# SmartCard.net
KiCad netlist of a schematic drawn in Altium Designer
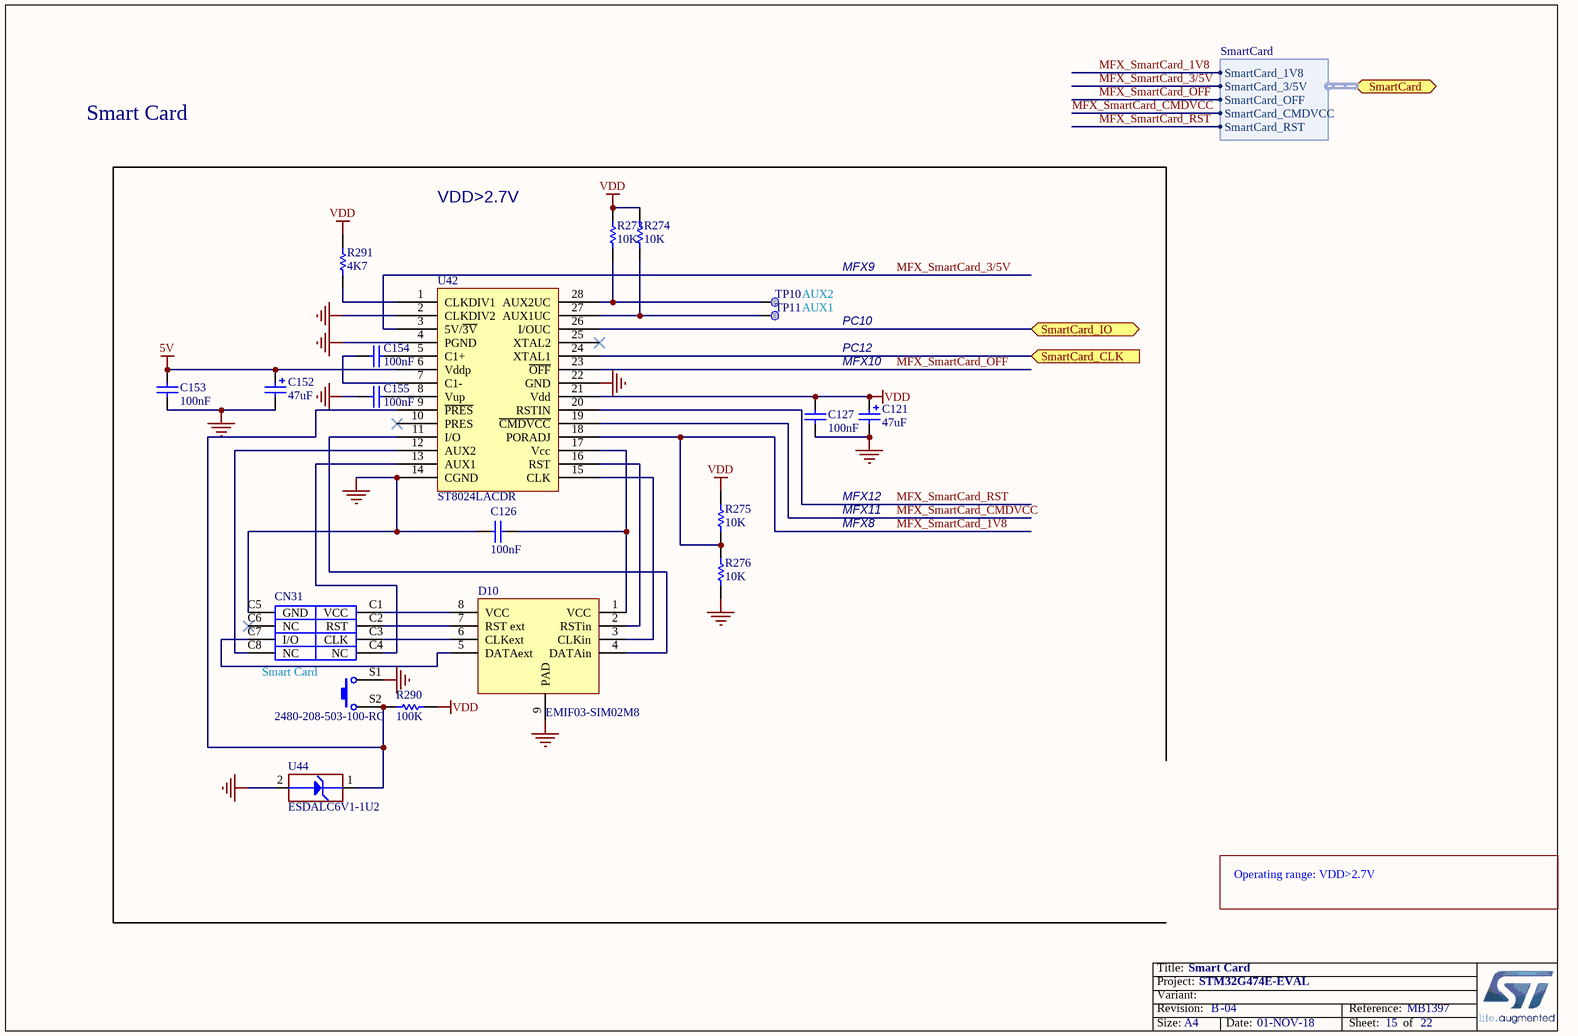
[diagram p0: SmartCard.SchDoc]

(export (version "E")
  (design (tool "Eeschema 10.0.6"))
  (components
    (comp (ref "C121")
      (value "47uF")
      (footprint "CPOL_TAJ-C_2312_H2P6")
      (description "Capacitor, Tantalum, 47uF, 16V, 10%, TypeC")
      (fields
        (field (name "INTERNAL_PART_NUMBER") "MCD-00559")
        (field (name "MANUFACTURER_PART_NUMBER") "TAJC476K016RNJ")
        (field (name "PROVIDED_BY") "SUBCO")
      )
      (libsource (lib "MCD_PARTS_database") (part "Cap_POL_TANA"))
    )
    (comp (ref "C126")
      (value "100nF")
      (footprint "C0603")
      (description "Capacitor, MLCC, 100nF, 16V, X7R, 10%, 0603, T=0,8mm")
      (fields
        (field (name "INTERNAL_PART_NUMBER") "MCD-00211")
        (field (name "MANUFACTURER_PART_NUMBER") "CC0603KRX7R7BB104")
        (field (name "PROVIDED_BY") "SUBCO")
      )
      (libsource (lib "MCD_PARTS_database") (part "Capacitor"))
    )
    (comp (ref "C127")
      (value "100nF")
      (footprint "C0603")
      (description "Capacitor, MLCC, 100nF, 16V, X7R, 10%, 0603, T=0,8mm")
      (fields
        (field (name "INTERNAL_PART_NUMBER") "MCD-00211")
        (field (name "MANUFACTURER_PART_NUMBER") "CC0603KRX7R7BB104")
        (field (name "PROVIDED_BY") "SUBCO")
      )
      (libsource (lib "MCD_PARTS_database") (part "Capacitor"))
    )
    (comp (ref "C152")
      (value "47uF")
      (footprint "CPOL_TAJ-C_2312_H2P6")
      (description "Capacitor, Tantalum, 47uF, 16V, 10%, TypeC")
      (fields
        (field (name "INTERNAL_PART_NUMBER") "MCD-00559")
        (field (name "MANUFACTURER_PART_NUMBER") "TAJC476K016RNJ")
        (field (name "PROVIDED_BY") "SUBCO")
      )
      (libsource (lib "MCD_PARTS_database") (part "Cap_POL_TANA"))
    )
    (comp (ref "C153")
      (value "100nF")
      (footprint "C0603")
      (description "Capacitor, MLCC, 100nF, 16V, X7R, 10%, 0603, T=0,8mm")
      (fields
        (field (name "INTERNAL_PART_NUMBER") "MCD-00211")
        (field (name "MANUFACTURER_PART_NUMBER") "CC0603KRX7R7BB104")
        (field (name "PROVIDED_BY") "SUBCO")
      )
      (libsource (lib "MCD_PARTS_database") (part "Capacitor"))
    )
    (comp (ref "C154")
      (value "100nF")
      (footprint "C0603")
      (description "Capacitor, MLCC, 100nF, 16V, X7R, 10%, 0603, T=0,8mm")
      (fields
        (field (name "INTERNAL_PART_NUMBER") "MCD-00211")
        (field (name "MANUFACTURER_PART_NUMBER") "CC0603KRX7R7BB104")
        (field (name "PROVIDED_BY") "SUBCO")
      )
      (libsource (lib "MCD_PARTS_database") (part "Capacitor"))
    )
    (comp (ref "C155")
      (value "100nF")
      (footprint "C0603")
      (description "Capacitor, MLCC, 100nF, 16V, X7R, 10%, 0603, T=0,8mm")
      (fields
        (field (name "INTERNAL_PART_NUMBER") "MCD-00211")
        (field (name "MANUFACTURER_PART_NUMBER") "CC0603KRX7R7BB104")
        (field (name "PROVIDED_BY") "SUBCO")
      )
      (libsource (lib "MCD_PARTS_database") (part "Capacitor"))
    )
    (comp (ref "CN31")
      (value "2480-208-503-100-RC")
      (footprint "CON_CARD-SOCKET_GUANG-LIAN-WEI_2480-208-503-100-RC")
      (description "IC Card Socket 8 pin, SMT Open for Smartcard")
      (fields
        (field (name "INTERNAL_PART_NUMBER") "MCD-01175")
        (field (name "MANUFACTURER") "GUANG LIAN WEI")
        (field (name "PROVIDED_BY") "Subcon")
      )
      (libsource (lib "MCD_Temp_EZH") (part "Smart_card_2480-208-503-100-RC"))
    )
    (comp (ref "D10")
      (value "EMIF03-SIM02M8")
      (footprint "ESD_UQFN8-EPAD_1P7X1P5_P040")
      (description "3 line IPAD, EMI filter for SIM card applications")
      (fields
        (field (name "INTERNAL_PART_NUMBER") "MCD-01229")
        (field (name "MANUFACTURER") "STMICROELECTRONICS")
        (field (name "PROVIDED_BY") "SUBCO with ST control")
      )
      (libsource (lib "MCD_PARTS_database") (part "EMIF03-SIM02M8"))
    )
    (comp (ref "R273")
      (value "10K")
      (footprint "R0603")
      (description "Resistor,10K,0603,1%,1/10W")
      (fields
        (field (name "INTERNAL_PART_NUMBER") "MCD-00220")
        (field (name "MANUFACTURER_PART_NUMBER") "RC0603FR-0710KL")
        (field (name "PROVIDED_BY") "SUBCO")
      )
      (libsource (lib "MCD_PARTS_database") (part "Resistor"))
    )
    (comp (ref "R274")
      (value "10K")
      (footprint "R0603")
      (description "Resistor,10K,0603,1%,1/10W")
      (fields
        (field (name "INTERNAL_PART_NUMBER") "MCD-00220")
        (field (name "MANUFACTURER_PART_NUMBER") "RC0603FR-0710KL")
        (field (name "PROVIDED_BY") "SUBCO")
      )
      (libsource (lib "MCD_PARTS_database") (part "Resistor"))
    )
    (comp (ref "R275")
      (value "10K")
      (footprint "R0603")
      (description "Resistor,10K,0603,1%,1/10W")
      (fields
        (field (name "INTERNAL_PART_NUMBER") "MCD-00220")
        (field (name "MANUFACTURER_PART_NUMBER") "RC0603FR-0710KL")
        (field (name "PROVIDED_BY") "SUBCO")
      )
      (libsource (lib "MCD_PARTS_database") (part "Resistor"))
    )
    (comp (ref "R276")
      (value "10K")
      (footprint "R0603")
      (description "Resistor,10K,0603,1%,1/10W")
      (fields
        (field (name "INTERNAL_PART_NUMBER") "MCD-00220")
        (field (name "MANUFACTURER_PART_NUMBER") "RC0603FR-0710KL")
        (field (name "PROVIDED_BY") "SUBCO")
      )
      (libsource (lib "MCD_PARTS_database") (part "Resistor"))
    )
    (comp (ref "R290")
      (value "100K")
      (footprint "R0603")
      (description "Resistor,100K,0603,1%,1/10W")
      (fields
        (field (name "INTERNAL_PART_NUMBER") "MCD-00223")
        (field (name "MANUFACTURER_PART_NUMBER") "RC0603FR-07100KL")
        (field (name "PROVIDED_BY") "SUBCO")
      )
      (libsource (lib "MCD_PARTS_database") (part "Resistor"))
    )
    (comp (ref "R291")
      (value "4K7")
      (footprint "R0402")
      (description "Resistor,4K7,0402,1%,1/16W")
      (fields
        (field (name "INTERNAL_PART_NUMBER") "MCD-00065")
        (field (name "MANUFACTURER_PART_NUMBER") "RC0402FR-074K7L")
        (field (name "PROVIDED_BY") "SUBCO")
      )
      (libsource (lib "MCD_PARTS_database") (part "Resistor"))
    )
    (comp (ref "TP10")
      (value "Test Point")
      (footprint "TP_SMD_1MM")
      (description "Test Point 1mm")
      (fields (field (name "INTERNAL_PART_NUMBER") "MCD-00074") (field (name "MANUFACTURER") "n/a"))
      (libsource (lib "MCD_PARTS_database") (part "Test Point"))
    )
    (comp (ref "TP11")
      (value "Test Point")
      (footprint "TP_SMD_1MM")
      (description "Test Point 1mm")
      (fields (field (name "INTERNAL_PART_NUMBER") "MCD-00074") (field (name "MANUFACTURER") "n/a"))
      (libsource (lib "MCD_PARTS_database") (part "Test Point"))
    )
    (comp (ref "U42")
      (value "ST8024LACDR")
      (footprint "ICC_SO28_18P10X7P60_P127")
      (description "Smartcard interfaces")
      (fields
        (field (name "INTERNAL_PART_NUMBER") "MCD-01162")
        (field (name "MANUFACTURER") "STMICROELECTRONICS")
        (field (name "PROVIDED_BY") "SUBCO with ST control")
      )
      (libsource (lib "MCD_PARTS_database") (part "ST8024CTR"))
    )
    (comp (ref "U44")
      (value "ESDALC6V1-1U2")
      (footprint "ESD_ST0201")
      (description "ESD protection 6V1")
      (fields
        (field (name "INTERNAL_PART_NUMBER") "MCD-00170")
        (field (name "MANUFACTURER") "STMICROELECTRONICS")
        (field (name "PROVIDED_BY") "SUBCO with ST control")
      )
      (libsource (lib "MCD_PARTS_database") (part "ESD-TRANSIL"))
    )
  )
  (nets
    (net (code "2") (name "/MFX_SmartCard_1V8") (class "Default")
      (node (ref "R275") (pin "1") (pinfunction "1_1") (pintype "passive"))
      (node (ref "R276") (pin "2") (pinfunction "2_2") (pintype "passive"))
      (node (ref "U42") (pin "18") (pinfunction "PORADJ_18") (pintype "passive"))
    )
    (net (code "3") (name "/MFX_SmartCard_3{slash}5V") (class "Default")
      (node (ref "U42") (pin "3") (pinfunction "5V/~{3V}_3") (pintype "passive"))
    )
    (net (code "4") (name "/MFX_SmartCard_CMDVCC") (class "Default")
      (node (ref "U42") (pin "19") (pinfunction "~{CMDVCC}_19") (pintype "passive"))
    )
    (net (code "5") (name "/MFX_SmartCard_OFF") (class "Default")
      (node (ref "U42") (pin "23") (pinfunction "~{OFF}_23") (pintype "passive"))
    )
    (net (code "6") (name "/MFX_SmartCard_RST") (class "Default")
      (node (ref "U42") (pin "20") (pinfunction "RSTIN_20") (pintype "passive"))
    )
    (net (code "7") (name "/SmartCard_CLK") (class "Default")
      (node (ref "U42") (pin "24") (pinfunction "XTAL1_24") (pintype "passive"))
    )
    (net (code "8") (name "/SmartCard_IO") (class "Default")
      (node (ref "U42") (pin "26") (pinfunction "I/OUC_26") (pintype "passive"))
    )
    (net (code "10") (name "5V") (class "Default")
      (node (ref "C152") (pin "1") (pinfunction "1_1") (pintype "passive"))
      (node (ref "C153") (pin "2") (pinfunction "2_2") (pintype "passive"))
      (node (ref "U42") (pin "6") (pinfunction "Vddp_6") (pintype "passive"))
    )
    (net (code "11") (name "GND") (class "Default")
      (node (ref "C121") (pin "2") (pinfunction "2_2") (pintype "passive"))
      (node (ref "C126") (pin "2") (pinfunction "2_2") (pintype "passive"))
      (node (ref "C127") (pin "1") (pinfunction "1_1") (pintype "passive"))
      (node (ref "C152") (pin "2") (pinfunction "2_2") (pintype "passive"))
      (node (ref "C153") (pin "1") (pinfunction "1_1") (pintype "passive"))
      (node (ref "C155") (pin "2") (pinfunction "2_2") (pintype "passive"))
      (node (ref "CN31") (pin "C5") (pinfunction "GND_C5") (pintype "passive"))
      (node (ref "CN31") (pin "S1") (pintype "passive"))
      (node (ref "D10") (pin "9") (pinfunction "PAD_9") (pintype "passive"))
      (node (ref "R276") (pin "1") (pinfunction "1_1") (pintype "passive"))
      (node (ref "U42") (pin "14") (pinfunction "CGND_14") (pintype "passive"))
      (node (ref "U42") (pin "2") (pinfunction "CLKDIV2_2") (pintype "passive"))
      (node (ref "U42") (pin "22") (pinfunction "GND_22") (pintype "passive"))
      (node (ref "U42") (pin "4") (pinfunction "PGND_4") (pintype "passive"))
      (node (ref "U44") (pin "2") (pinfunction "GND_2") (pintype "passive"))
    )
    (net (code "12") (name "Net-(CN31-CLK)") (class "Default")
      (node (ref "CN31") (pin "C3") (pinfunction "CLK_C3") (pintype "passive"))
      (node (ref "D10") (pin "6") (pinfunction "CLKext_6") (pintype "passive"))
    )
    (net (code "13") (name "Net-(CN31-I{slash}O)") (class "Default")
      (node (ref "CN31") (pin "C7") (pinfunction "I/O_C7") (pintype "passive"))
      (node (ref "D10") (pin "5") (pinfunction "DATAext_5") (pintype "passive"))
    )
    (net (code "14") (name "Net-(CN31-RST)") (class "Default")
      (node (ref "CN31") (pin "C2") (pinfunction "RST_C2") (pintype "passive"))
      (node (ref "D10") (pin "7") (pinfunction "RST_ext_7") (pintype "passive"))
    )
    (net (code "15") (name "Net-(CN31-VCC)") (class "Default")
      (node (ref "CN31") (pin "C1") (pinfunction "VCC_C1") (pintype "passive"))
      (node (ref "D10") (pin "8") (pinfunction "VCC_8") (pintype "passive"))
    )
    (net (code "16") (name "Net-(D10-CLKin)") (class "Default")
      (node (ref "D10") (pin "3") (pinfunction "CLKin_3") (pintype "passive"))
      (node (ref "U42") (pin "15") (pinfunction "CLK_15") (pintype "passive"))
    )
    (net (code "17") (name "Net-(D10-DATAin)") (class "Default")
      (node (ref "D10") (pin "4") (pinfunction "DATAin_4") (pintype "passive"))
      (node (ref "U42") (pin "11") (pinfunction "I/O_11") (pintype "passive"))
    )
    (net (code "18") (name "Net-(D10-RSTin)") (class "Default")
      (node (ref "D10") (pin "2") (pinfunction "RSTin_2") (pintype "passive"))
      (node (ref "U42") (pin "16") (pinfunction "RST_16") (pintype "passive"))
    )
    (net (code "19") (name "Net-(U42-AUX1)") (class "Default")
      (node (ref "CN31") (pin "C4") (pinfunction "NC_C4") (pintype "passive"))
      (node (ref "U42") (pin "13") (pinfunction "AUX1_13") (pintype "passive"))
    )
    (net (code "20") (name "Net-(U42-AUX1UC)") (class "Default")
      (node (ref "R274") (pin "1") (pinfunction "1_1") (pintype "passive"))
      (node (ref "TP11") (pin "1") (pinfunction "1_1") (pintype "passive"))
      (node (ref "U42") (pin "27") (pinfunction "AUX1UC_27") (pintype "passive"))
    )
    (net (code "21") (name "Net-(U42-AUX2)") (class "Default")
      (node (ref "CN31") (pin "C8") (pinfunction "NC_C8") (pintype "passive"))
      (node (ref "U42") (pin "12") (pinfunction "AUX2_12") (pintype "passive"))
    )
    (net (code "22") (name "Net-(U42-AUX2UC)") (class "Default")
      (node (ref "R273") (pin "1") (pinfunction "1_1") (pintype "passive"))
      (node (ref "TP10") (pin "1") (pinfunction "1_1") (pintype "passive"))
      (node (ref "U42") (pin "28") (pinfunction "AUX2UC_28") (pintype "passive"))
    )
    (net (code "23") (name "Net-(U42-C1+)") (class "Default")
      (node (ref "C154") (pin "1") (pinfunction "1_1") (pintype "passive"))
      (node (ref "U42") (pin "5") (pinfunction "C1+_5") (pintype "passive"))
    )
    (net (code "24") (name "Net-(U42-C1-)") (class "Default")
      (node (ref "C154") (pin "2") (pinfunction "2_2") (pintype "passive"))
      (node (ref "U42") (pin "7") (pinfunction "C1-_7") (pintype "passive"))
    )
    (net (code "25") (name "Net-(U42-CLKDIV1)") (class "Default")
      (node (ref "R291") (pin "1") (pinfunction "1_1") (pintype "passive"))
      (node (ref "U42") (pin "1") (pinfunction "CLKDIV1_1") (pintype "passive"))
    )
    (net (code "26") (name "Net-(U42-Vcc)") (class "Default")
      (node (ref "C126") (pin "1") (pinfunction "1_1") (pintype "passive"))
      (node (ref "D10") (pin "1") (pinfunction "VCC_1") (pintype "passive"))
      (node (ref "U42") (pin "17") (pinfunction "Vcc_17") (pintype "passive"))
    )
    (net (code "27") (name "Net-(U42-Vup)") (class "Default")
      (node (ref "C155") (pin "1") (pinfunction "1_1") (pintype "passive"))
      (node (ref "U42") (pin "8") (pinfunction "Vup_8") (pintype "passive"))
    )
    (net (code "28") (name "Net-(U42-~{PRES})") (class "Default")
      (node (ref "CN31") (pin "S2") (pintype "passive"))
      (node (ref "R290") (pin "1") (pinfunction "1_1") (pintype "passive"))
      (node (ref "U42") (pin "9") (pinfunction "~{PRES}_9") (pintype "passive"))
      (node (ref "U44") (pin "1") (pinfunction "IO1_1") (pintype "passive"))
    )
    (net (code "29") (name "VDD") (class "Default")
      (node (ref "C121") (pin "1") (pinfunction "1_1") (pintype "passive"))
      (node (ref "C127") (pin "2") (pinfunction "2_2") (pintype "passive"))
      (node (ref "R273") (pin "2") (pinfunction "2_2") (pintype "passive"))
      (node (ref "R274") (pin "2") (pinfunction "2_2") (pintype "passive"))
      (node (ref "R275") (pin "2") (pinfunction "2_2") (pintype "passive"))
      (node (ref "R290") (pin "2") (pinfunction "2_2") (pintype "passive"))
      (node (ref "R291") (pin "2") (pinfunction "2_2") (pintype "passive"))
      (node (ref "U42") (pin "21") (pinfunction "Vdd_21") (pintype "passive"))
    )
    (net (code "30") (name "unconnected-(CN31-NC-PadC6)") (class "Default")
      (node (ref "CN31") (pin "C6") (pinfunction "NC_C6") (pintype "passive+no_connect"))
    )
    (net (code "31") (name "unconnected-(U42-PRES-Pad10)") (class "Default")
      (node (ref "U42") (pin "10") (pinfunction "PRES_10") (pintype "passive+no_connect"))
    )
    (net (code "32") (name "unconnected-(U42-XTAL2-Pad25)") (class "Default")
      (node (ref "U42") (pin "25") (pinfunction "XTAL2_25") (pintype "passive+no_connect"))
    )
  )
)
